# 05-RESET.net
KiCad netlist of a schematic drawn in Altium Designer
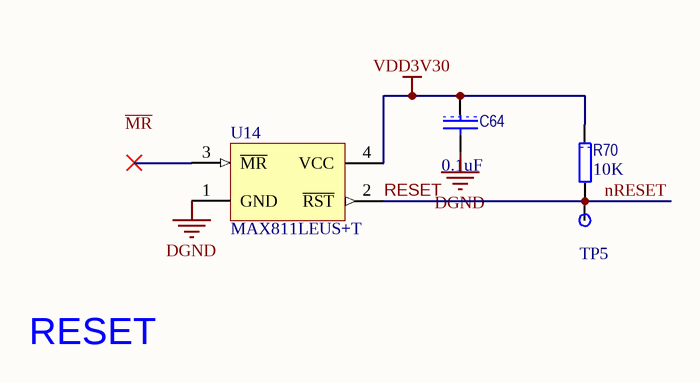
[diagram p0: 05-RESET.SchDoc]

(export (version "E")
  (design (tool "Eeschema 10.0.6"))
  (components
    (comp (ref "C64")
      (value "0.1uF")
      (footprint "1608[0603]C")
      (description "多层陶瓷电容器MLCC - SMD/SMT 0603 0.1uF 50volts X7R 10%")
      (fields (field (name "MANUFACTURER") "TDK") (field (name "MANUFACTURER PART NUMBER") "C1608X7R1H104K"))
      (libsource (lib "*") (part "CAP"))
    )
    (comp (ref "R70")
      (value "10K")
      (footprint "1608[0603]R")
      (description "厚膜电阻器 - SMD 1/10watt 10Kohms 1%")
      (fields
        (field (name "MANUFACTURER") "Vishay / Dale")
        (field (name "MANUFACTURER PART NUMBER") "CRCW060310K0FKEA")
      )
      (libsource (lib "10K 1%") (part "RES"))
    )
    (comp (ref "TP5")
      (value "TP")
      (footprint "TP")
      (description "Test Point")
      (libsource (lib "S3C2440V9") (part "Test Point"))
    )
    (comp (ref "U14")
      (value "MAX811LEUS+T")
      (footprint "SOT143_N")
      (description "监控电路 4-Pin uPower Voltage Monitor")
      (fields (field (name "MANUFACTURER") "Maxim Integrated"))
      (libsource (lib "Maxim Power Mgt Supervisory Circuit") (part "MAX811-EUS-T"))
    )
  )
  (nets
    (net (code "1") (name "/RESET") (class "Default")
      (node (ref "R70") (pin "2") (pinfunction "2_2") (pintype "passive"))
      (node (ref "TP5") (pin "1") (pinfunction "TestPoint_1") (pintype "passive"))
      (node (ref "U14") (pin "2") (pinfunction "~{RST}_2") (pintype "output"))
    )
    (net (code "3") (name "DGND") (class "Default")
      (node (ref "C64") (pin "2") (pinfunction "2_2") (pintype "passive"))
      (node (ref "U14") (pin "1") (pinfunction "GND_1") (pintype "power_in"))
    )
    (net (code "4") (name "VDD3V30") (class "Default")
      (node (ref "C64") (pin "1") (pinfunction "1_1") (pintype "passive"))
      (node (ref "R70") (pin "1") (pinfunction "1_1") (pintype "passive"))
      (node (ref "U14") (pin "4") (pinfunction "VCC_4") (pintype "power_in"))
    )
    (net (code "5") (name "unconnected-(U14-~{MR}-Pad3)") (class "Default")
      (node (ref "U14") (pin "3") (pinfunction "~{MR}_3") (pintype "input+no_connect"))
    )
  )
)
